# CAN-breakout-v2.net
KiCad netlist of a schematic drawn in EAGLE
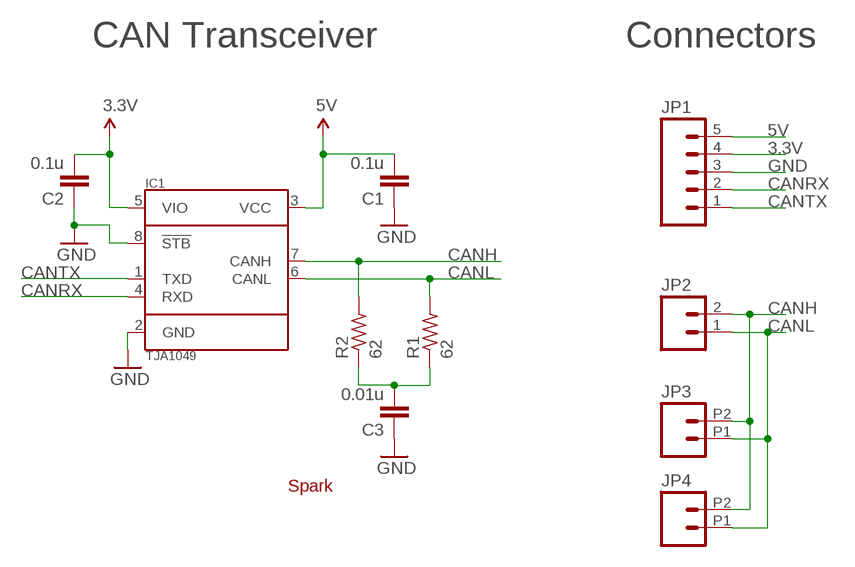
[diagram p0: schematic, sheet 1]

(export (version "E")
  (design (tool "Eeschema 10.0.6"))
  (components
    (comp (ref "C1")
      (value "0.1u")
      (footprint "eagle-import:C1206")
      (fields (field (name "PARTNO") "12065C104KAT2A"))
      (libsource (lib "eagle-import") (part "C-EUC1206"))
    )
    (comp (ref "C2")
      (value "0.1u")
      (footprint "eagle-import:C1206")
      (fields (field (name "PARTNO") "12065C104KAT2A"))
      (libsource (lib "eagle-import") (part "C-EUC1206"))
    )
    (comp (ref "C3")
      (value "0.01u")
      (footprint "eagle-import:C1206")
      (fields (field (name "PARTNO") "12065C103KAT2A"))
      (libsource (lib "eagle-import") (part "C-EUC1206"))
    )
    (comp (ref "IC1")
      (value "TJA1049")
      (footprint "eagle-import:SO8")
      (fields (field (name "PARTNO") "TJA1049T-118"))
      (libsource (lib "eagle-import") (part "TJA1049"))
    )
    (comp (ref "JP1")
      (value "M05PTH")
      (footprint "eagle-import:1X05")
      (fields (field (name "PARTNO") "PREC005SAAN-RC"))
      (libsource (lib "eagle-import") (part "M05PTH"))
    )
    (comp (ref "JP2")
      (value "M02PTH")
      (footprint "eagle-import:1X02")
      (fields (field (name "PARTNO") "PREC002SAAN-RC"))
      (libsource (lib "eagle-import") (part "M02PTH"))
    )
    (comp (ref "JP3")
      (value "M022.54MM_SCREWTERM")
      (footprint "eagle-import:1X02_2.54_SCREWTERM")
      (fields (field (name "PARTNO") "OSTVN02A150"))
      (libsource (lib "eagle-import") (part "M022.54MM_SCREWTERM"))
    )
    (comp (ref "JP4")
      (value "M022.54MM_SCREWTERM")
      (footprint "eagle-import:1X02_2.54_SCREWTERM")
      (fields (field (name "PARTNO") "OSTVN02A150"))
      (libsource (lib "eagle-import") (part "M022.54MM_SCREWTERM"))
    )
    (comp (ref "R1")
      (value "62")
      (footprint "eagle-import:R1206")
      (fields (field (name "PARTNO") "RC1206FR-0762RL"))
      (libsource (lib "eagle-import") (part "R-US_R1206"))
    )
    (comp (ref "R2")
      (value "62")
      (footprint "eagle-import:R1206")
      (fields (field (name "PARTNO") "RC1206FR-0762RL"))
      (libsource (lib "eagle-import") (part "R-US_R1206"))
    )
    (comp (ref "U$3")
      (value "SPARK_LOGO2")
      (footprint "eagle-import:SPARK_LOGO2")
      (libsource (lib "eagle-import") (part "SPARK_LOGO2"))
    )
  )
  (nets
    (net (code "1") (name "/CANH") (class "Default")
      (node (ref "IC1") (pin "7") (pinfunction "CANH_7") (pintype "bidirectional"))
      (node (ref "JP2") (pin "2") (pinfunction "2_2") (pintype "passive"))
      (node (ref "JP3") (pin "P2") (pinfunction "2_P2") (pintype "passive"))
      (node (ref "JP4") (pin "P2") (pinfunction "2_P2") (pintype "passive"))
      (node (ref "R2") (pin "2") (pinfunction "2_2") (pintype "passive"))
    )
    (net (code "2") (name "/CANL") (class "Default")
      (node (ref "IC1") (pin "6") (pinfunction "CANL_6") (pintype "bidirectional"))
      (node (ref "JP2") (pin "1") (pinfunction "1_1") (pintype "passive"))
      (node (ref "JP3") (pin "P1") (pinfunction "1_P1") (pintype "passive"))
      (node (ref "JP4") (pin "P1") (pinfunction "1_P1") (pintype "passive"))
      (node (ref "R1") (pin "2") (pinfunction "2_2") (pintype "passive"))
    )
    (net (code "3") (name "/CANRX") (class "Default")
      (node (ref "IC1") (pin "4") (pinfunction "RXD_4") (pintype "bidirectional"))
      (node (ref "JP1") (pin "2") (pinfunction "2_2") (pintype "passive"))
    )
    (net (code "4") (name "/CANTX") (class "Default")
      (node (ref "IC1") (pin "1") (pinfunction "TXD_1") (pintype "bidirectional"))
      (node (ref "JP1") (pin "1") (pinfunction "1_1") (pintype "passive"))
    )
    (net (code "5") (name "3.3V") (class "Default")
      (node (ref "C2") (pin "2") (pinfunction "2_2") (pintype "passive"))
      (node (ref "IC1") (pin "5") (pinfunction "VIO_5") (pintype "bidirectional"))
      (node (ref "JP1") (pin "4") (pinfunction "4_4") (pintype "passive"))
    )
    (net (code "6") (name "5V") (class "Default")
      (node (ref "C1") (pin "2") (pinfunction "2_2") (pintype "passive"))
      (node (ref "IC1") (pin "3") (pinfunction "VCC_3") (pintype "bidirectional"))
      (node (ref "JP1") (pin "5") (pinfunction "5_5") (pintype "passive"))
    )
    (net (code "7") (name "GND") (class "Default")
      (node (ref "C1") (pin "1") (pinfunction "1_1") (pintype "passive"))
      (node (ref "C2") (pin "1") (pinfunction "1_1") (pintype "passive"))
      (node (ref "C3") (pin "1") (pinfunction "1_1") (pintype "passive"))
      (node (ref "IC1") (pin "2") (pinfunction "GND_2") (pintype "bidirectional"))
      (node (ref "IC1") (pin "8") (pinfunction "~{STB}_8") (pintype "bidirectional"))
      (node (ref "JP1") (pin "3") (pinfunction "3_3") (pintype "passive"))
    )
    (net (code "8") (name "Net-(C3-Pad2)") (class "Default")
      (node (ref "C3") (pin "2") (pinfunction "2_2") (pintype "passive"))
      (node (ref "R1") (pin "1") (pinfunction "1_1") (pintype "passive"))
      (node (ref "R2") (pin "1") (pinfunction "1_1") (pintype "passive"))
    )
  )
)
